# Commuta_PCBv1.net
KiCad netlist of a schematic drawn in EasyEDA Pro
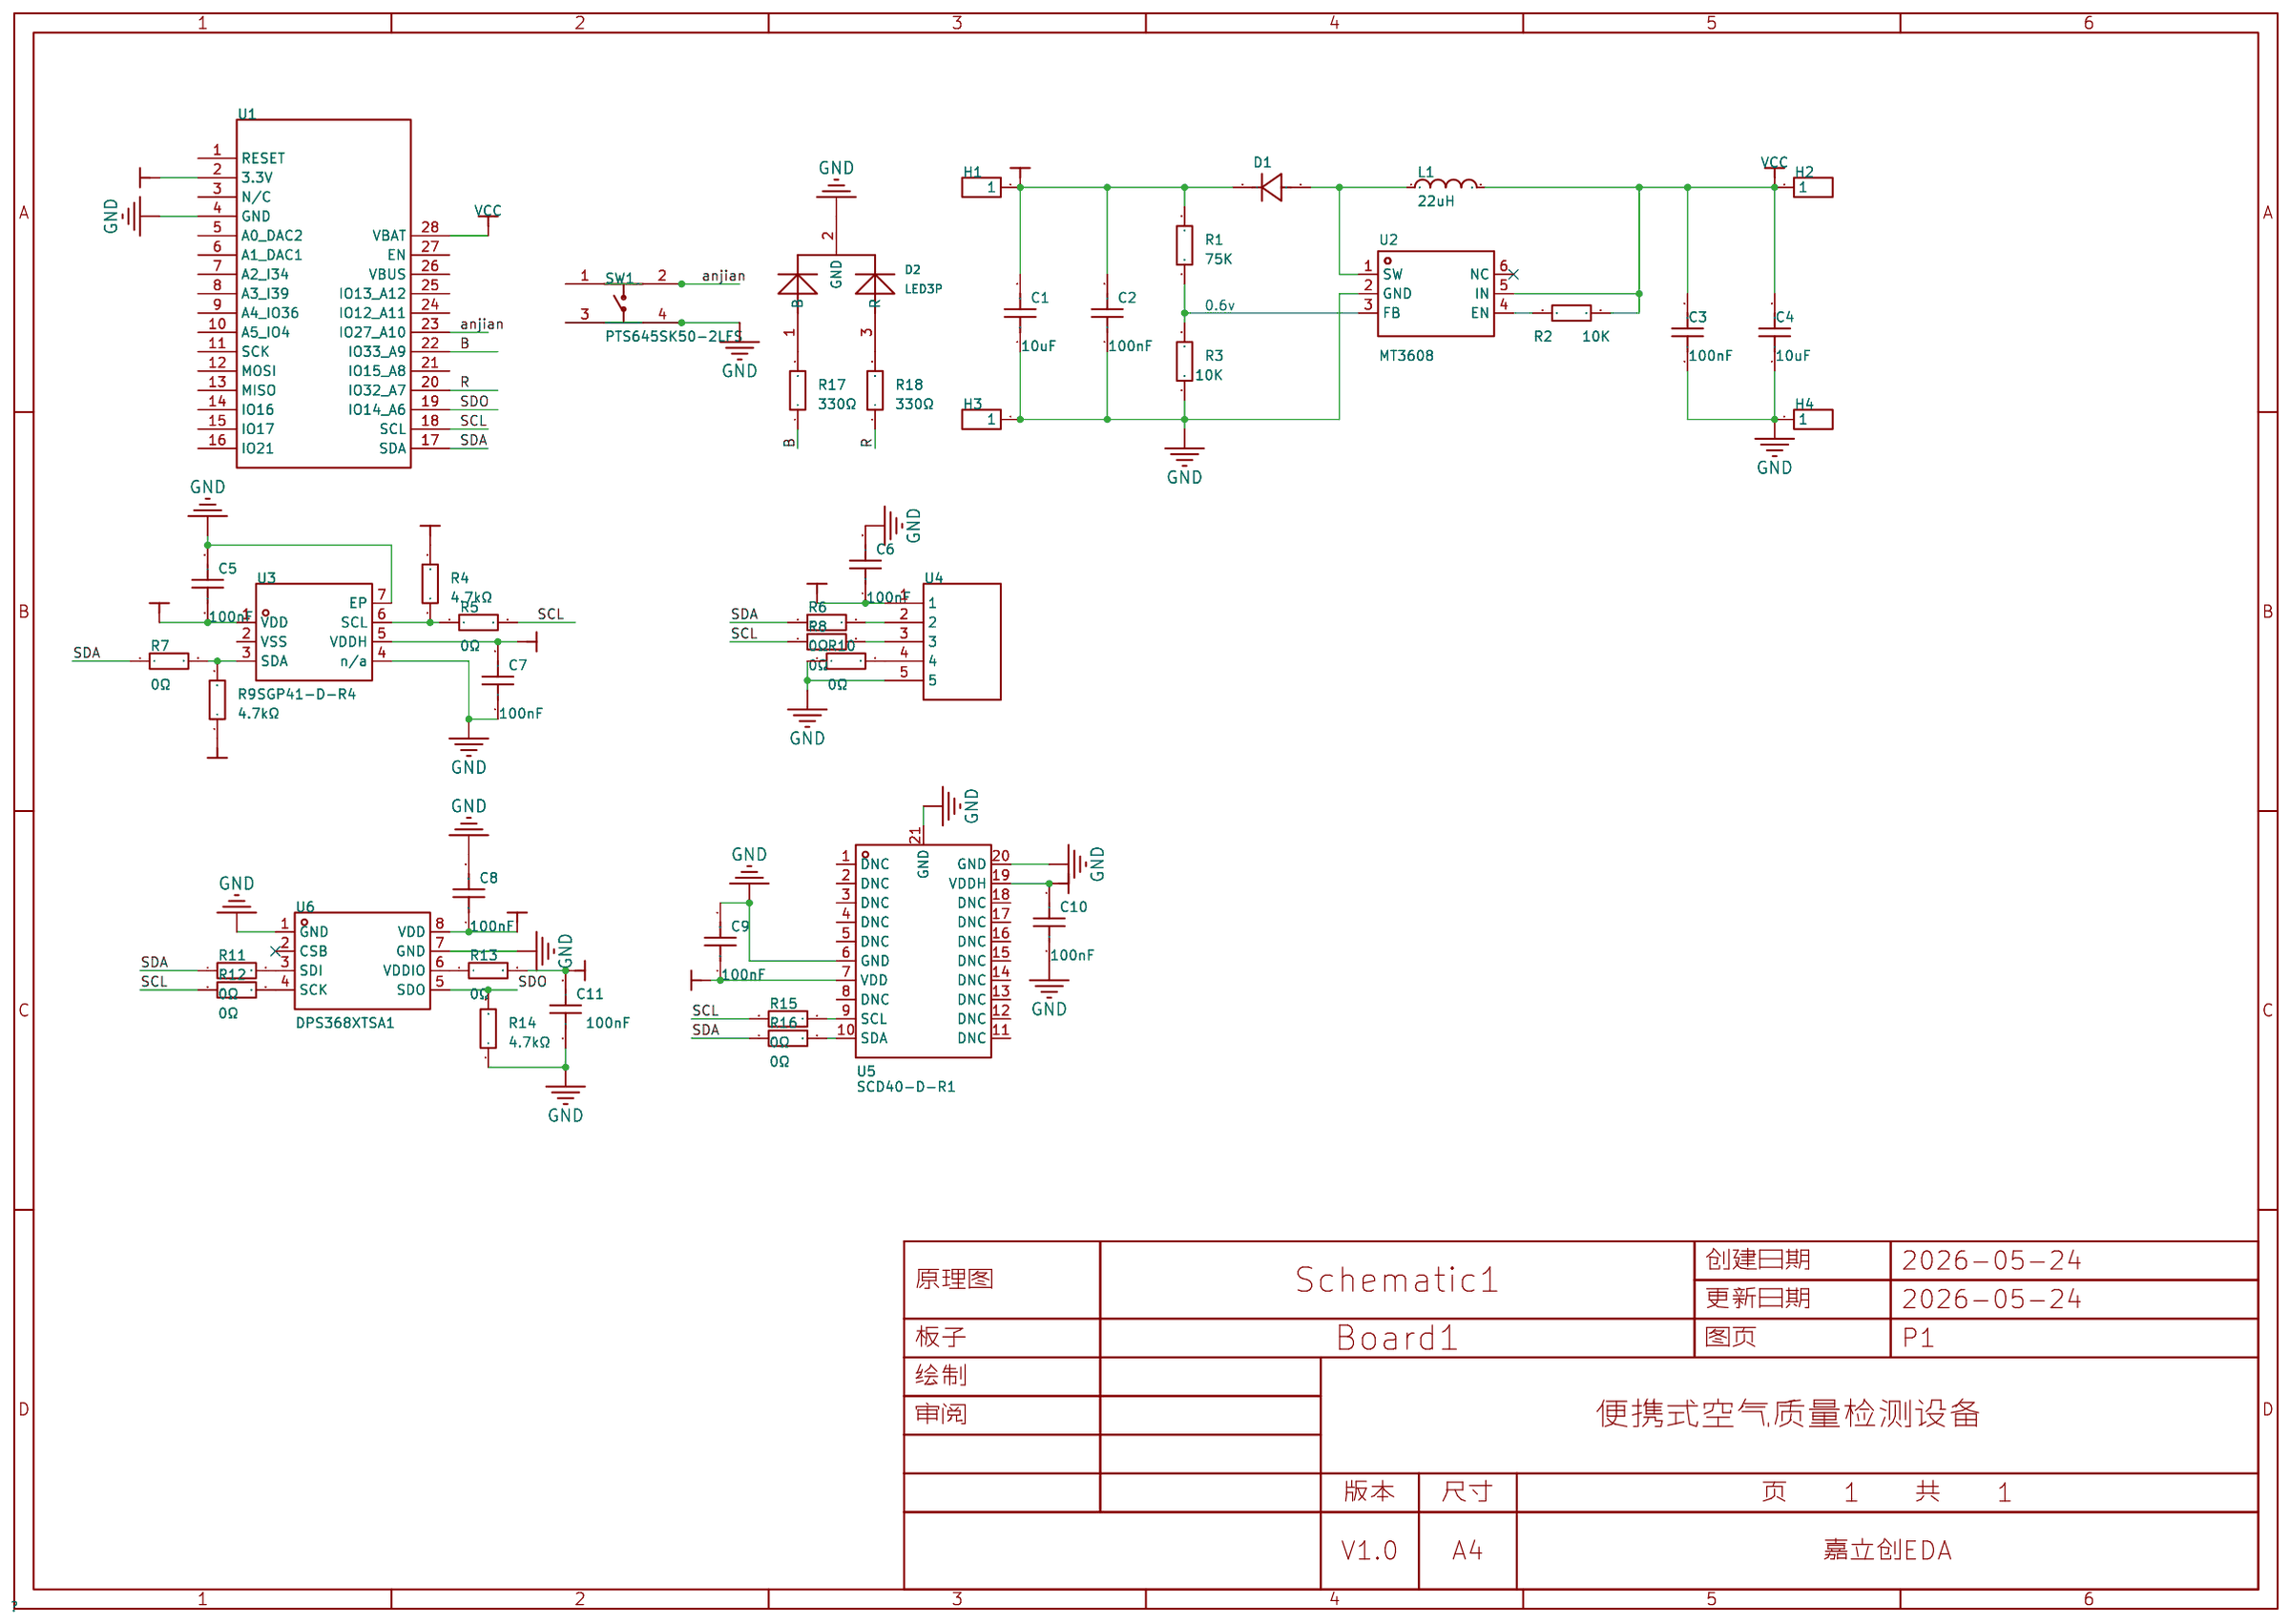
[diagram p0: schematic sheet]

(export (version "E")
  (design (tool "Eeschema 10.0.6"))
  (components
    (comp (ref "C1")
      (value "10uF")
      (footprint "easyedapro:C0603")
      (libsource (lib "easyedapro") (part "CapAcitance"))
    )
    (comp (ref "C2")
      (value "100nF")
      (footprint "easyedapro:C0603")
      (libsource (lib "easyedapro") (part "CapAcitance"))
    )
    (comp (ref "C3")
      (value "100nF")
      (footprint "easyedapro:C0603")
      (libsource (lib "easyedapro") (part "CapAcitance"))
    )
    (comp (ref "C4")
      (value "10uF")
      (footprint "easyedapro:C0603")
      (libsource (lib "easyedapro") (part "CapAcitance"))
    )
    (comp (ref "C5")
      (value "100nF")
      (footprint "easyedapro:C0603")
      (libsource (lib "easyedapro") (part "CapAcitance"))
    )
    (comp (ref "C6")
      (value "100nF")
      (footprint "easyedapro:C0603")
      (libsource (lib "easyedapro") (part "CapAcitance"))
    )
    (comp (ref "C7")
      (value "100nF")
      (footprint "easyedapro:C0603")
      (libsource (lib "easyedapro") (part "CapAcitance"))
    )
    (comp (ref "C8")
      (value "100nF")
      (footprint "easyedapro:C0603")
      (libsource (lib "easyedapro") (part "CapAcitance"))
    )
    (comp (ref "C9")
      (value "100nF")
      (footprint "easyedapro:C0603")
      (libsource (lib "easyedapro") (part "CapAcitance"))
    )
    (comp (ref "C10")
      (value "100nF")
      (footprint "easyedapro:C0603")
      (libsource (lib "easyedapro") (part "CapAcitance"))
    )
    (comp (ref "C11")
      (value "100nF")
      (footprint "easyedapro:C0603")
      (libsource (lib "easyedapro") (part "CapAcitance"))
    )
    (comp (ref "D1")
      (value "~")
      (footprint "easyedapro:SMA_1N4007")
      (libsource (lib "easyedapro") (part "D_1N4007"))
    )
    (comp (ref "D2")
      (value "LED3P")
      (footprint "easyedapro:LED3P")
      (libsource (lib "easyedapro") (part "LED3P"))
    )
    (comp (ref "H1")
      (value "~")
      (footprint "easyedapro:HDR-TH_1P-V-M_XKB_X4611WV-01I-C28D40")
      (libsource (lib "easyedapro") (part "HDR_1x1"))
    )
    (comp (ref "H2")
      (value "~")
      (footprint "easyedapro:HDR-TH_1P-V-M_XKB_X4611WV-01I-C28D40")
      (libsource (lib "easyedapro") (part "HDR_1x1"))
    )
    (comp (ref "H3")
      (value "~")
      (footprint "easyedapro:HDR-TH_1P-V-M_XKB_X4611WV-01I-C28D40")
      (libsource (lib "easyedapro") (part "HDR_1x1"))
    )
    (comp (ref "H4")
      (value "~")
      (footprint "easyedapro:HDR-TH_1P-V-M_XKB_X4611WV-01I-C28D40")
      (libsource (lib "easyedapro") (part "HDR_1x1"))
    )
    (comp (ref "L1")
      (value "22uH")
      (footprint "easyedapro:IND-SMD_L6.0-W5.2_SUMIDA_CDH53")
      (description "电感值:22uH;精度:±20%;额定电流:2A;饱和电流(Isat):2.5A;类型:一体成型电感;")
      (fields (field (name "Manufacturer Part") "PCR0530-220-M") (field (name "Manufacturer") "JIERR(捷而瑞)"))
      (libsource (lib "easyedapro") (part "PCR0530-220-M"))
    )
    (comp (ref "R1") (value "75K") (footprint "easyedapro:R0603") (libsource (lib "easyedapro") (part "电阻")))
    (comp (ref "R2") (value "10K") (footprint "easyedapro:R0603") (libsource (lib "easyedapro") (part "电阻")))
    (comp (ref "R3") (value "10K") (footprint "easyedapro:R0603") (libsource (lib "easyedapro") (part "电阻")))
    (comp (ref "R4")
      (value "4.7kΩ")
      (footprint "easyedapro:R0603")
      (fields (field (name "Manufacturer Part") "RC0603FR-074K7L") (field (name "Manufacturer") "YAGEO(国巨)"))
      (libsource (lib "easyedapro") (part "RC0603FR-074K7L"))
    )
    (comp (ref "R5")
      (value "0Ω")
      (footprint "easyedapro:R0603")
      (fields (field (name "Manufacturer Part") "RC0603FR-070RL") (field (name "Manufacturer") "YAGEO(国巨)"))
      (libsource (lib "easyedapro") (part "RC0603FR-070RL"))
    )
    (comp (ref "R6")
      (value "0Ω")
      (footprint "easyedapro:R0603")
      (fields (field (name "Manufacturer Part") "RC0603FR-070RL") (field (name "Manufacturer") "YAGEO(国巨)"))
      (libsource (lib "easyedapro") (part "RC0603FR-070RL"))
    )
    (comp (ref "R7")
      (value "0Ω")
      (footprint "easyedapro:R0603")
      (fields (field (name "Manufacturer Part") "RC0603FR-070RL") (field (name "Manufacturer") "YAGEO(国巨)"))
      (libsource (lib "easyedapro") (part "RC0603FR-070RL"))
    )
    (comp (ref "R8")
      (value "0Ω")
      (footprint "easyedapro:R0603")
      (fields (field (name "Manufacturer Part") "RC0603FR-070RL") (field (name "Manufacturer") "YAGEO(国巨)"))
      (libsource (lib "easyedapro") (part "RC0603FR-070RL"))
    )
    (comp (ref "R9")
      (value "4.7kΩ")
      (footprint "easyedapro:R0603")
      (fields (field (name "Manufacturer Part") "RC0603FR-074K7L") (field (name "Manufacturer") "YAGEO(国巨)"))
      (libsource (lib "easyedapro") (part "RC0603FR-074K7L"))
    )
    (comp (ref "R10")
      (value "0Ω")
      (footprint "easyedapro:R0603")
      (fields (field (name "Manufacturer Part") "RC0603FR-070RL") (field (name "Manufacturer") "YAGEO(国巨)"))
      (libsource (lib "easyedapro") (part "RC0603FR-070RL"))
    )
    (comp (ref "R11")
      (value "0Ω")
      (footprint "easyedapro:R0603")
      (fields (field (name "Manufacturer Part") "RC0603FR-070RL") (field (name "Manufacturer") "YAGEO(国巨)"))
      (libsource (lib "easyedapro") (part "RC0603FR-070RL"))
    )
    (comp (ref "R12")
      (value "0Ω")
      (footprint "easyedapro:R0603")
      (fields (field (name "Manufacturer Part") "RC0603FR-070RL") (field (name "Manufacturer") "YAGEO(国巨)"))
      (libsource (lib "easyedapro") (part "RC0603FR-070RL"))
    )
    (comp (ref "R13")
      (value "0Ω")
      (footprint "easyedapro:R0603")
      (fields (field (name "Manufacturer Part") "RC0603FR-070RL") (field (name "Manufacturer") "YAGEO(国巨)"))
      (libsource (lib "easyedapro") (part "RC0603FR-070RL"))
    )
    (comp (ref "R14")
      (value "4.7kΩ")
      (footprint "easyedapro:R0603")
      (fields (field (name "Manufacturer Part") "RC0603FR-074K7L") (field (name "Manufacturer") "YAGEO(国巨)"))
      (libsource (lib "easyedapro") (part "RC0603FR-074K7L"))
    )
    (comp (ref "R15")
      (value "0Ω")
      (footprint "easyedapro:R0603")
      (fields (field (name "Manufacturer Part") "RC0603FR-070RL") (field (name "Manufacturer") "YAGEO(国巨)"))
      (libsource (lib "easyedapro") (part "RC0603FR-070RL"))
    )
    (comp (ref "R16")
      (value "0Ω")
      (footprint "easyedapro:R0603")
      (fields (field (name "Manufacturer Part") "RC0603FR-070RL") (field (name "Manufacturer") "YAGEO(国巨)"))
      (libsource (lib "easyedapro") (part "RC0603FR-070RL"))
    )
    (comp (ref "R17")
      (value "330Ω")
      (footprint "easyedapro:R1206")
      (fields
        (field (name "Manufacturer Part") "1206W4J0331T5E")
        (field (name "Manufacturer") "UNI-ROYAL(厚声)")
      )
      (libsource (lib "easyedapro") (part "1206W4J0331T5E"))
    )
    (comp (ref "R18")
      (value "330Ω")
      (footprint "easyedapro:R1206")
      (fields
        (field (name "Manufacturer Part") "1206W4J0331T5E")
        (field (name "Manufacturer") "UNI-ROYAL(厚声)")
      )
      (libsource (lib "easyedapro") (part "1206W4J0331T5E"))
    )
    (comp (ref "SW1")
      (value "PTS645SK50-2LFS")
      (footprint "easyedapro:KEY-TH_4P-L6.0-W6.0-P4.50-LS6.50")
      (fields (field (name "Manufacturer") "C&K"))
      (libsource (lib "easyedapro") (part "PTS645SK50-2LFS"))
    )
    (comp (ref "U1")
      (value "~")
      (footprint "easyedapro:HUZZAH32 ESP32")
      (libsource (lib "easyedapro") (part "HUZZAH32 ESP32"))
    )
    (comp (ref "U2")
      (value "MT3608")
      (footprint "easyedapro:SOT-23-6_L2.9-W1.6-P0.95-LS2.8-BL")
      (description "功能类型:升压型;输入电压:2V~24V;输出电压:28V;输出电流(最大值):-;")
      (fields (field (name "Manufacturer") "西安航天民芯"))
      (libsource (lib "easyedapro") (part "MT3608"))
    )
    (comp (ref "U3")
      (value "SGP41-D-R4")
      (footprint "easyedapro:DFN-6_L2.4-W2.4-P0.80-TL-EP")
      (fields (field (name "Manufacturer") "Sensirion(瑞士盛思锐)"))
      (libsource (lib "easyedapro") (part "SGP41-D-R4"))
    )
    (comp (ref "U4") (value "~") (description "SPS30传感器") (libsource (lib "easyedapro") (part "SPS30传感器")))
    (comp (ref "U5")
      (value "SCD40-D-R1")
      (footprint "easyedapro:LGA-20_L10.1-W10.1-P1.25-TL")
      (fields (field (name "Manufacturer") "Sensirion(瑞士盛思锐)"))
      (libsource (lib "easyedapro") (part "SCD40-D-R1"))
    )
    (comp (ref "U6")
      (value "DPS368XTSA1")
      (footprint "easyedapro:LGA-8_L2.5-W2.0-P0.65-TR_DPS368")
      (fields (field (name "Manufacturer") "Infineon(英飞凌)"))
      (libsource (lib "easyedapro") (part "DPS368XTSA1"))
    )
  )
  (nets
    (net (code "1") (name "+3.3V") (class "Default")
      (node (ref "C10") (pin "2") (pinfunction "2_2") (pintype "input"))
      (node (ref "C11") (pin "2") (pinfunction "2_2") (pintype "input"))
      (node (ref "C5") (pin "1") (pinfunction "1_1") (pintype "input"))
      (node (ref "C7") (pin "2") (pinfunction "2_2") (pintype "input"))
      (node (ref "C8") (pin "1") (pinfunction "1_1") (pintype "input"))
      (node (ref "C9") (pin "1") (pinfunction "1_1") (pintype "input"))
      (node (ref "R13") (pin "2") (pinfunction "2_2") (pintype "input"))
      (node (ref "R4") (pin "2") (pinfunction "2_2") (pintype "input"))
      (node (ref "R9") (pin "1") (pinfunction "1_1") (pintype "input"))
      (node (ref "U1") (pin "2") (pinfunction "3.3V_2") (pintype "unspecified"))
      (node (ref "U3") (pin "1") (pinfunction "VDD_1") (pintype "unspecified"))
      (node (ref "U3") (pin "5") (pinfunction "VDDH_5") (pintype "unspecified"))
      (node (ref "U5") (pin "19") (pinfunction "VDDH_19") (pintype "unspecified"))
      (node (ref "U5") (pin "7") (pinfunction "VDD_7") (pintype "unspecified"))
      (node (ref "U6") (pin "8") (pinfunction "VDD_8") (pintype "unspecified"))
    )
    (net (code "2") (name "+5V") (class "Default")
      (node (ref "C1") (pin "2") (pinfunction "2_2") (pintype "input"))
      (node (ref "C2") (pin "2") (pinfunction "2_2") (pintype "input"))
      (node (ref "C6") (pin "1") (pinfunction "1_1") (pintype "input"))
      (node (ref "D1") (pin "1") (pinfunction "K_1") (pintype "input"))
      (node (ref "H1") (pin "1") (pinfunction "1_1") (pintype "unspecified"))
      (node (ref "R1") (pin "2") (pinfunction "2_2") (pintype "input"))
      (node (ref "U4") (pin "1") (pinfunction "1_1") (pintype "input"))
    )
    (net (code "3") (name "/B") (class "Default")
      (node (ref "R17") (pin "1") (pinfunction "1_1") (pintype "input"))
      (node (ref "U1") (pin "22") (pinfunction "IO33_A9_22") (pintype "unspecified"))
    )
    (net (code "4") (name "/R") (class "Default")
      (node (ref "R18") (pin "1") (pinfunction "1_1") (pintype "input"))
      (node (ref "U1") (pin "20") (pinfunction "IO32_A7_20") (pintype "unspecified"))
    )
    (net (code "5") (name "/SCL") (class "Default")
      (node (ref "R12") (pin "1") (pinfunction "1_1") (pintype "input"))
      (node (ref "R15") (pin "2") (pinfunction "2_2") (pintype "input"))
      (node (ref "R5") (pin "2") (pinfunction "2_2") (pintype "input"))
      (node (ref "R8") (pin "1") (pinfunction "1_1") (pintype "input"))
      (node (ref "U1") (pin "18") (pinfunction "SCL_18") (pintype "unspecified"))
    )
    (net (code "6") (name "/SDA") (class "Default")
      (node (ref "R11") (pin "1") (pinfunction "1_1") (pintype "input"))
      (node (ref "R16") (pin "1") (pinfunction "1_1") (pintype "input"))
      (node (ref "R6") (pin "1") (pinfunction "1_1") (pintype "input"))
      (node (ref "R7") (pin "1") (pinfunction "1_1") (pintype "input"))
      (node (ref "U1") (pin "17") (pinfunction "SDA_17") (pintype "unspecified"))
    )
    (net (code "7") (name "/SDO") (class "Default")
      (node (ref "R14") (pin "2") (pinfunction "2_2") (pintype "input"))
      (node (ref "U1") (pin "19") (pinfunction "IO14_A6_19") (pintype "unspecified"))
      (node (ref "U6") (pin "5") (pinfunction "SDO_5") (pintype "unspecified"))
    )
    (net (code "8") (name "/anjian") (class "Default")
      (node (ref "SW1") (pin "1") (pinfunction "1_1") (pintype "unspecified"))
      (node (ref "SW1") (pin "2") (pinfunction "2_2") (pintype "unspecified"))
      (node (ref "U1") (pin "23") (pinfunction "IO27_A10_23") (pintype "unspecified"))
    )
    (net (code "9") (name "GND") (class "Default")
      (node (ref "C1") (pin "1") (pinfunction "1_1") (pintype "input"))
      (node (ref "C10") (pin "1") (pinfunction "1_1") (pintype "input"))
      (node (ref "C11") (pin "1") (pinfunction "1_1") (pintype "input"))
      (node (ref "C2") (pin "1") (pinfunction "1_1") (pintype "input"))
      (node (ref "C3") (pin "1") (pinfunction "1_1") (pintype "input"))
      (node (ref "C4") (pin "1") (pinfunction "1_1") (pintype "input"))
      (node (ref "C5") (pin "2") (pinfunction "2_2") (pintype "input"))
      (node (ref "C6") (pin "2") (pinfunction "2_2") (pintype "input"))
      (node (ref "C7") (pin "1") (pinfunction "1_1") (pintype "input"))
      (node (ref "C8") (pin "2") (pinfunction "2_2") (pintype "input"))
      (node (ref "C9") (pin "2") (pinfunction "2_2") (pintype "input"))
      (node (ref "D2") (pin "2") (pinfunction "GND_2") (pintype "unspecified"))
      (node (ref "H3") (pin "1") (pinfunction "1_1") (pintype "unspecified"))
      (node (ref "H4") (pin "1") (pinfunction "1_1") (pintype "unspecified"))
      (node (ref "R10") (pin "1") (pinfunction "1_1") (pintype "input"))
      (node (ref "R14") (pin "1") (pinfunction "1_1") (pintype "input"))
      (node (ref "R3") (pin "1") (pinfunction "1_1") (pintype "input"))
      (node (ref "SW1") (pin "3") (pinfunction "3_3") (pintype "unspecified"))
      (node (ref "SW1") (pin "4") (pinfunction "4_4") (pintype "unspecified"))
      (node (ref "U1") (pin "4") (pinfunction "GND_4") (pintype "unspecified"))
      (node (ref "U2") (pin "2") (pinfunction "GND_2") (pintype "input"))
      (node (ref "U3") (pin "4") (pinfunction "n/a_4") (pintype "unspecified"))
      (node (ref "U3") (pin "7") (pinfunction "EP_7") (pintype "unspecified"))
      (node (ref "U4") (pin "5") (pinfunction "5_5") (pintype "input"))
      (node (ref "U5") (pin "20") (pinfunction "GND_20") (pintype "unspecified"))
      (node (ref "U5") (pin "21") (pinfunction "GND_21") (pintype "unspecified"))
      (node (ref "U5") (pin "6") (pinfunction "GND_6") (pintype "unspecified"))
      (node (ref "U6") (pin "1") (pinfunction "GND_1") (pintype "unspecified"))
      (node (ref "U6") (pin "7") (pinfunction "GND_7") (pintype "unspecified"))
    )
    (net (code "10") (name "Net-(D1-A)") (class "Default")
      (node (ref "D1") (pin "2") (pinfunction "A_2") (pintype "input"))
      (node (ref "L1") (pin "1") (pinfunction "1_1") (pintype "unspecified"))
      (node (ref "U2") (pin "1") (pinfunction "SW_1") (pintype "input"))
    )
    (net (code "11") (name "Net-(D2-B)") (class "Default")
      (node (ref "D2") (pin "1") (pinfunction "B_1") (pintype "unspecified"))
      (node (ref "R17") (pin "2") (pinfunction "2_2") (pintype "input"))
    )
    (net (code "12") (name "Net-(D2-R)") (class "Default")
      (node (ref "D2") (pin "3") (pinfunction "R_3") (pintype "unspecified"))
      (node (ref "R18") (pin "2") (pinfunction "2_2") (pintype "input"))
    )
    (net (code "13") (name "Net-(R6-Pad2)") (class "Default")
      (node (ref "R6") (pin "2") (pinfunction "2_2") (pintype "input"))
      (node (ref "U4") (pin "2") (pinfunction "2_2") (pintype "input"))
    )
    (net (code "14") (name "Net-(R8-Pad2)") (class "Default")
      (node (ref "R8") (pin "2") (pinfunction "2_2") (pintype "input"))
      (node (ref "U4") (pin "3") (pinfunction "3_3") (pintype "input"))
    )
    (net (code "15") (name "Net-(R10-Pad2)") (class "Default")
      (node (ref "R10") (pin "2") (pinfunction "2_2") (pintype "input"))
      (node (ref "U4") (pin "4") (pinfunction "4_4") (pintype "input"))
    )
    (net (code "16") (name "Net-(U2-EN)") (class "Default")
      (node (ref "R2") (pin "1") (pinfunction "1_1") (pintype "input"))
      (node (ref "U2") (pin "4") (pinfunction "EN_4") (pintype "input"))
    )
    (net (code "17") (name "Net-(U2-FB)") (class "Default")
      (node (ref "R1") (pin "1") (pinfunction "1_1") (pintype "input"))
      (node (ref "R3") (pin "2") (pinfunction "2_2") (pintype "input"))
      (node (ref "U2") (pin "3") (pinfunction "FB_3") (pintype "input"))
    )
    (net (code "18") (name "Net-(U3-SCL)") (class "Default")
      (node (ref "R4") (pin "1") (pinfunction "1_1") (pintype "input"))
      (node (ref "R5") (pin "1") (pinfunction "1_1") (pintype "input"))
      (node (ref "U3") (pin "6") (pinfunction "SCL_6") (pintype "unspecified"))
    )
    (net (code "19") (name "Net-(U3-SDA)") (class "Default")
      (node (ref "R7") (pin "2") (pinfunction "2_2") (pintype "input"))
      (node (ref "R9") (pin "2") (pinfunction "2_2") (pintype "input"))
      (node (ref "U3") (pin "3") (pinfunction "SDA_3") (pintype "unspecified"))
    )
    (net (code "20") (name "Net-(U5-SCL)") (class "Default")
      (node (ref "R15") (pin "1") (pinfunction "1_1") (pintype "input"))
      (node (ref "U5") (pin "9") (pinfunction "SCL_9") (pintype "unspecified"))
    )
    (net (code "21") (name "Net-(U5-SDA)") (class "Default")
      (node (ref "R16") (pin "2") (pinfunction "2_2") (pintype "input"))
      (node (ref "U5") (pin "10") (pinfunction "SDA_10") (pintype "unspecified"))
    )
    (net (code "22") (name "Net-(U6-SCK)") (class "Default")
      (node (ref "R12") (pin "2") (pinfunction "2_2") (pintype "input"))
      (node (ref "U6") (pin "4") (pinfunction "SCK_4") (pintype "unspecified"))
    )
    (net (code "23") (name "Net-(U6-SDI)") (class "Default")
      (node (ref "R11") (pin "2") (pinfunction "2_2") (pintype "input"))
      (node (ref "U6") (pin "3") (pinfunction "SDI_3") (pintype "unspecified"))
    )
    (net (code "24") (name "Net-(U6-VDDIO)") (class "Default")
      (node (ref "R13") (pin "1") (pinfunction "1_1") (pintype "input"))
      (node (ref "U6") (pin "6") (pinfunction "VDDIO_6") (pintype "unspecified"))
    )
    (net (code "25") (name "VCC") (class "Default")
      (node (ref "C3") (pin "2") (pinfunction "2_2") (pintype "input"))
      (node (ref "C4") (pin "2") (pinfunction "2_2") (pintype "input"))
      (node (ref "H2") (pin "1") (pinfunction "1_1") (pintype "unspecified"))
      (node (ref "L1") (pin "2") (pinfunction "2_2") (pintype "unspecified"))
      (node (ref "R2") (pin "2") (pinfunction "2_2") (pintype "input"))
      (node (ref "U1") (pin "28") (pinfunction "VBAT_28") (pintype "unspecified"))
      (node (ref "U2") (pin "5") (pinfunction "IN_5") (pintype "input"))
    )
    (net (code "26") (name "unconnected-(U1-A0_DAC2-Pad5)") (class "Default")
      (node (ref "U1") (pin "5") (pinfunction "A0_DAC2_5") (pintype "unspecified"))
    )
    (net (code "27") (name "unconnected-(U1-A1_DAC1-Pad6)") (class "Default")
      (node (ref "U1") (pin "6") (pinfunction "A1_DAC1_6") (pintype "unspecified"))
    )
    (net (code "28") (name "unconnected-(U1-A2_I34-Pad7)") (class "Default")
      (node (ref "U1") (pin "7") (pinfunction "A2_I34_7") (pintype "unspecified"))
    )
    (net (code "29") (name "unconnected-(U1-A3_I39-Pad8)") (class "Default")
      (node (ref "U1") (pin "8") (pinfunction "A3_I39_8") (pintype "unspecified"))
    )
    (net (code "30") (name "unconnected-(U1-A4_IO36-Pad9)") (class "Default")
      (node (ref "U1") (pin "9") (pinfunction "A4_IO36_9") (pintype "unspecified"))
    )
    (net (code "31") (name "unconnected-(U1-A5_IO4-Pad10)") (class "Default")
      (node (ref "U1") (pin "10") (pinfunction "A5_IO4_10") (pintype "unspecified"))
    )
    (net (code "32") (name "unconnected-(U1-EN-Pad27)") (class "Default")
      (node (ref "U1") (pin "27") (pinfunction "EN_27") (pintype "unspecified"))
    )
    (net (code "33") (name "unconnected-(U1-IO12_A11-Pad24)") (class "Default")
      (node (ref "U1") (pin "24") (pinfunction "IO12_A11_24") (pintype "unspecified"))
    )
    (net (code "34") (name "unconnected-(U1-IO13_A12-Pad25)") (class "Default")
      (node (ref "U1") (pin "25") (pinfunction "IO13_A12_25") (pintype "unspecified"))
    )
    (net (code "35") (name "unconnected-(U1-IO15_A8-Pad21)") (class "Default")
      (node (ref "U1") (pin "21") (pinfunction "IO15_A8_21") (pintype "unspecified"))
    )
    (net (code "36") (name "unconnected-(U1-IO16-Pad14)") (class "Default")
      (node (ref "U1") (pin "14") (pinfunction "IO16_14") (pintype "unspecified"))
    )
    (net (code "37") (name "unconnected-(U1-IO17-Pad15)") (class "Default")
      (node (ref "U1") (pin "15") (pinfunction "IO17_15") (pintype "unspecified"))
    )
    (net (code "38") (name "unconnected-(U1-IO21-Pad16)") (class "Default")
      (node (ref "U1") (pin "16") (pinfunction "IO21_16") (pintype "unspecified"))
    )
    (net (code "39") (name "unconnected-(U1-MISO-Pad13)") (class "Default")
      (node (ref "U1") (pin "13") (pinfunction "MISO_13") (pintype "unspecified"))
    )
    (net (code "40") (name "unconnected-(U1-MOSI-Pad12)") (class "Default")
      (node (ref "U1") (pin "12") (pinfunction "MOSI_12") (pintype "unspecified"))
    )
    (net (code "41") (name "unconnected-(U1-N{slash}C-Pad3)") (class "Default")
      (node (ref "U1") (pin "3") (pinfunction "N/C_3") (pintype "unspecified"))
    )
    (net (code "42") (name "unconnected-(U1-RESET-Pad1)") (class "Default")
      (node (ref "U1") (pin "1") (pinfunction "RESET_1") (pintype "unspecified"))
    )
    (net (code "43") (name "unconnected-(U1-SCK-Pad11)") (class "Default")
      (node (ref "U1") (pin "11") (pinfunction "SCK_11") (pintype "unspecified"))
    )
    (net (code "44") (name "unconnected-(U1-VBUS-Pad26)") (class "Default")
      (node (ref "U1") (pin "26") (pinfunction "VBUS_26") (pintype "unspecified"))
    )
    (net (code "45") (name "unconnected-(U2-NC-Pad6)") (class "Default")
      (node (ref "U2") (pin "6") (pinfunction "NC_6") (pintype "input+no_connect"))
    )
    (net (code "46") (name "unconnected-(U3-VSS-Pad2)") (class "Default")
      (node (ref "U3") (pin "2") (pinfunction "VSS_2") (pintype "unspecified"))
    )
    (net (code "47") (name "unconnected-(U5-DNC-Pad1)") (class "Default")
      (node (ref "U5") (pin "1") (pinfunction "DNC_1") (pintype "unspecified"))
    )
    (net (code "48") (name "unconnected-(U5-DNC-Pad2)") (class "Default")
      (node (ref "U5") (pin "2") (pinfunction "DNC_2") (pintype "unspecified"))
    )
    (net (code "49") (name "unconnected-(U5-DNC-Pad3)") (class "Default")
      (node (ref "U5") (pin "3") (pinfunction "DNC_3") (pintype "unspecified"))
    )
    (net (code "50") (name "unconnected-(U5-DNC-Pad4)") (class "Default")
      (node (ref "U5") (pin "4") (pinfunction "DNC_4") (pintype "unspecified"))
    )
    (net (code "51") (name "unconnected-(U5-DNC-Pad5)") (class "Default")
      (node (ref "U5") (pin "5") (pinfunction "DNC_5") (pintype "unspecified"))
    )
    (net (code "52") (name "unconnected-(U5-DNC-Pad8)") (class "Default")
      (node (ref "U5") (pin "8") (pinfunction "DNC_8") (pintype "unspecified"))
    )
    (net (code "53") (name "unconnected-(U5-DNC-Pad11)") (class "Default")
      (node (ref "U5") (pin "11") (pinfunction "DNC_11") (pintype "unspecified"))
    )
    (net (code "54") (name "unconnected-(U5-DNC-Pad12)") (class "Default")
      (node (ref "U5") (pin "12") (pinfunction "DNC_12") (pintype "unspecified"))
    )
    (net (code "55") (name "unconnected-(U5-DNC-Pad13)") (class "Default")
      (node (ref "U5") (pin "13") (pinfunction "DNC_13") (pintype "unspecified"))
    )
    (net (code "56") (name "unconnected-(U5-DNC-Pad14)") (class "Default")
      (node (ref "U5") (pin "14") (pinfunction "DNC_14") (pintype "unspecified"))
    )
    (net (code "57") (name "unconnected-(U5-DNC-Pad15)") (class "Default")
      (node (ref "U5") (pin "15") (pinfunction "DNC_15") (pintype "unspecified"))
    )
    (net (code "58") (name "unconnected-(U5-DNC-Pad16)") (class "Default")
      (node (ref "U5") (pin "16") (pinfunction "DNC_16") (pintype "unspecified"))
    )
    (net (code "59") (name "unconnected-(U5-DNC-Pad17)") (class "Default")
      (node (ref "U5") (pin "17") (pinfunction "DNC_17") (pintype "unspecified"))
    )
    (net (code "60") (name "unconnected-(U5-DNC-Pad18)") (class "Default")
      (node (ref "U5") (pin "18") (pinfunction "DNC_18") (pintype "unspecified"))
    )
    (net (code "61") (name "unconnected-(U6-CSB-Pad2)") (class "Default")
      (node (ref "U6") (pin "2") (pinfunction "CSB_2") (pintype "unspecified+no_connect"))
    )
  )
)
